# NAME_of_the_Game_NAND_Circuitry_v1.net
KiCad netlist of a schematic drawn in EAGLE
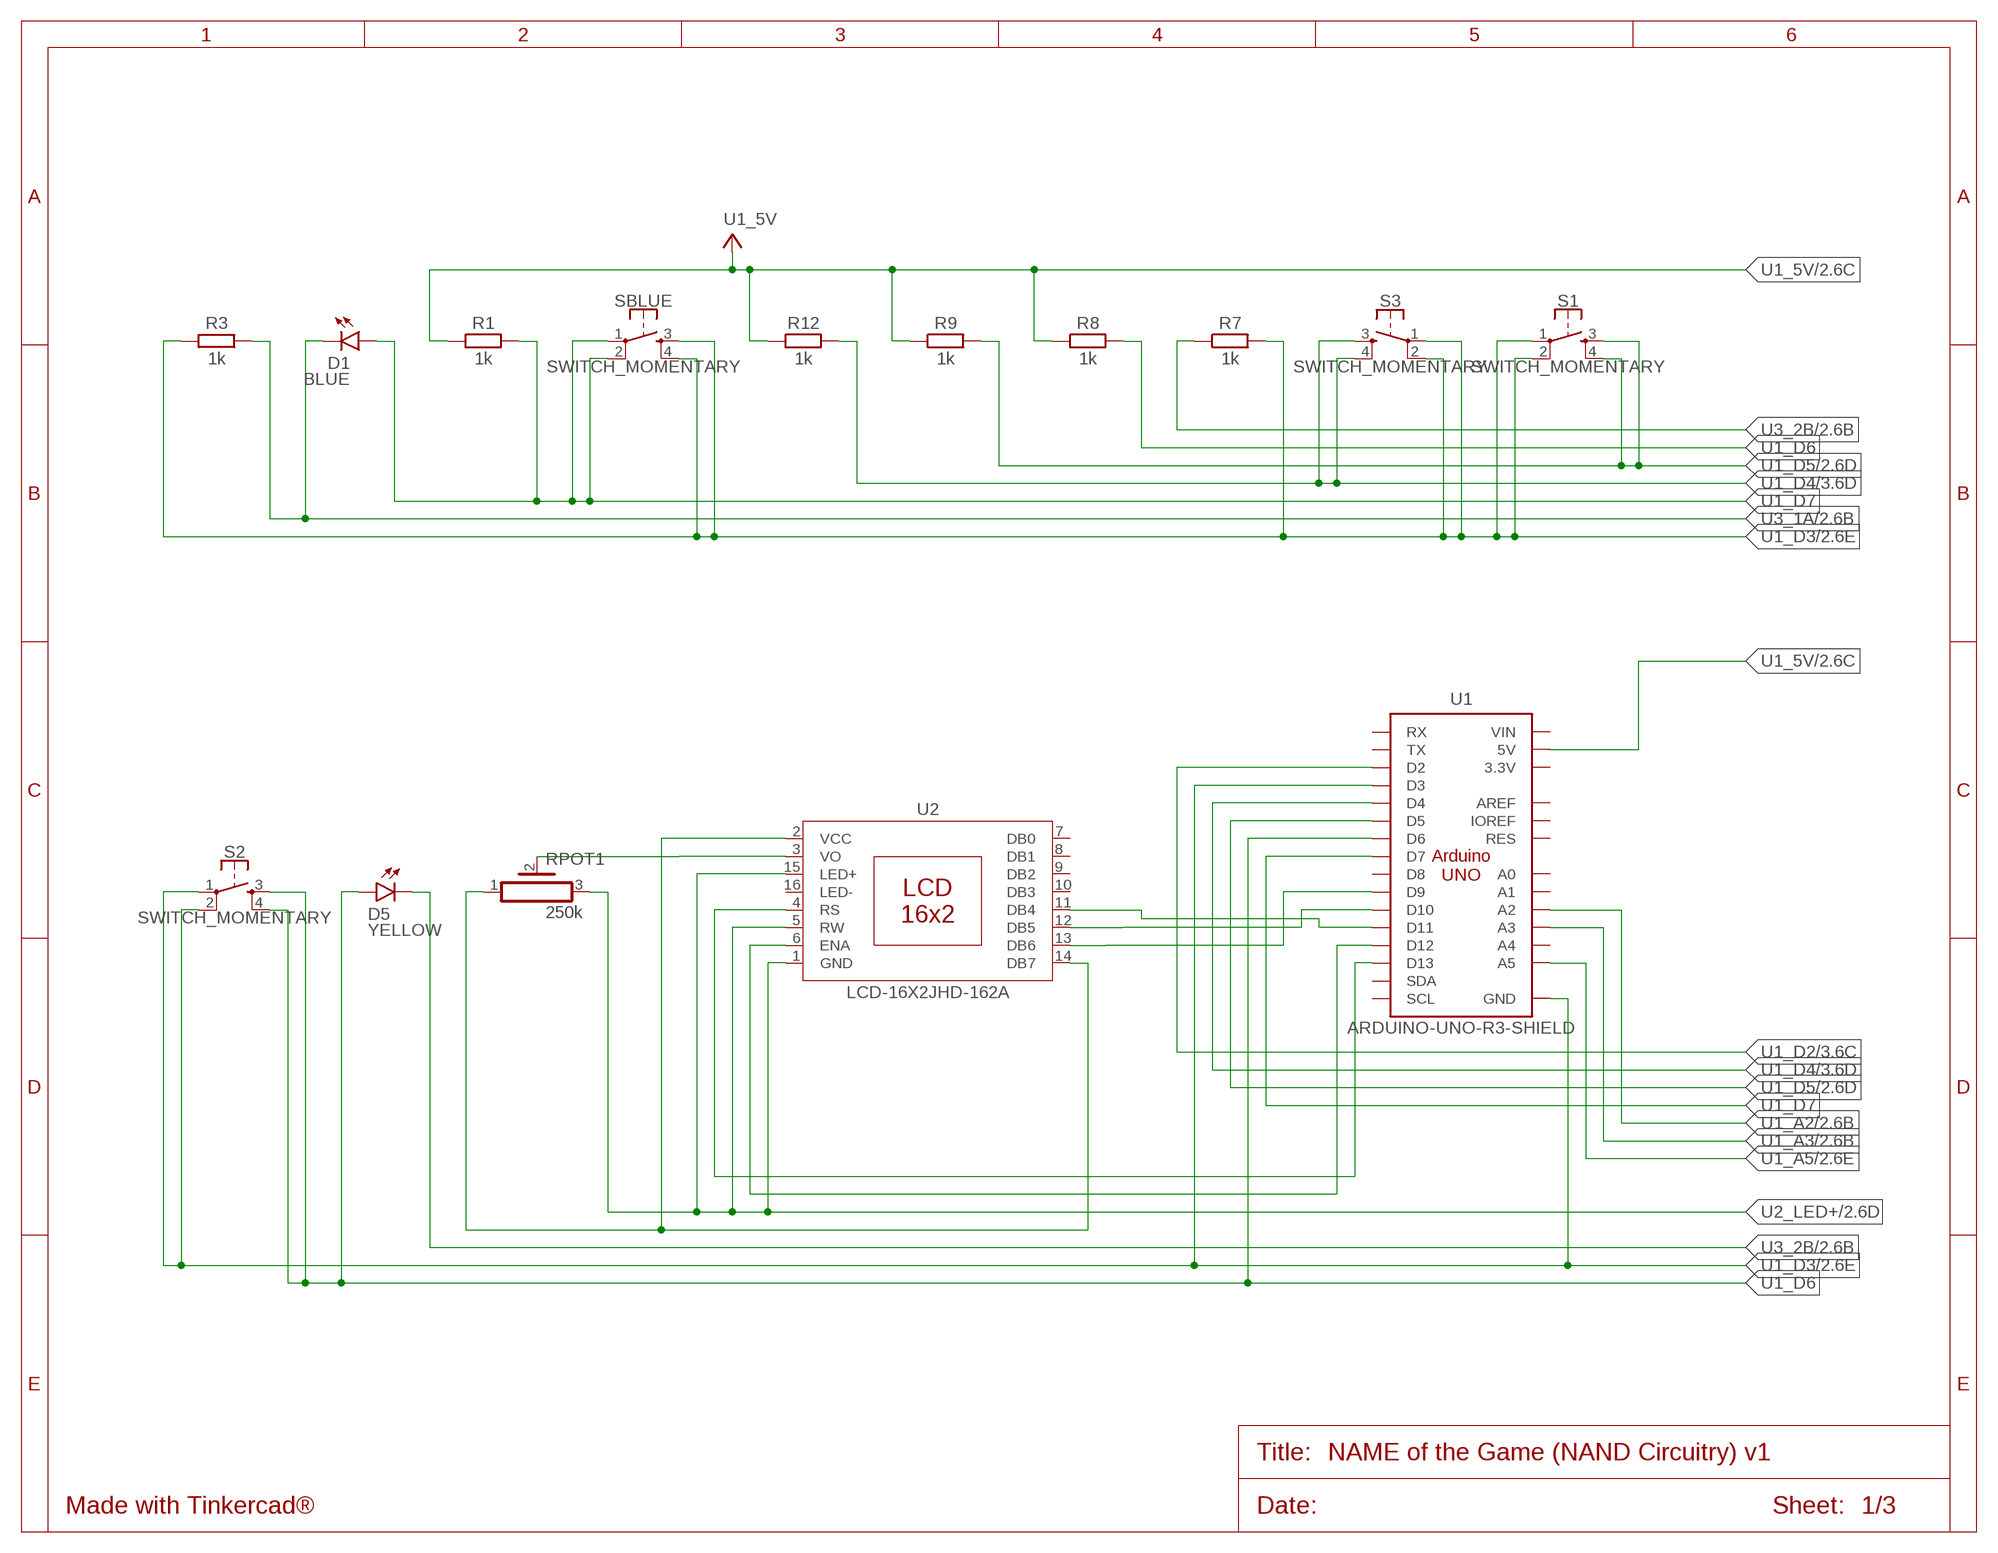
[diagram p0: schematic, sheet 1]
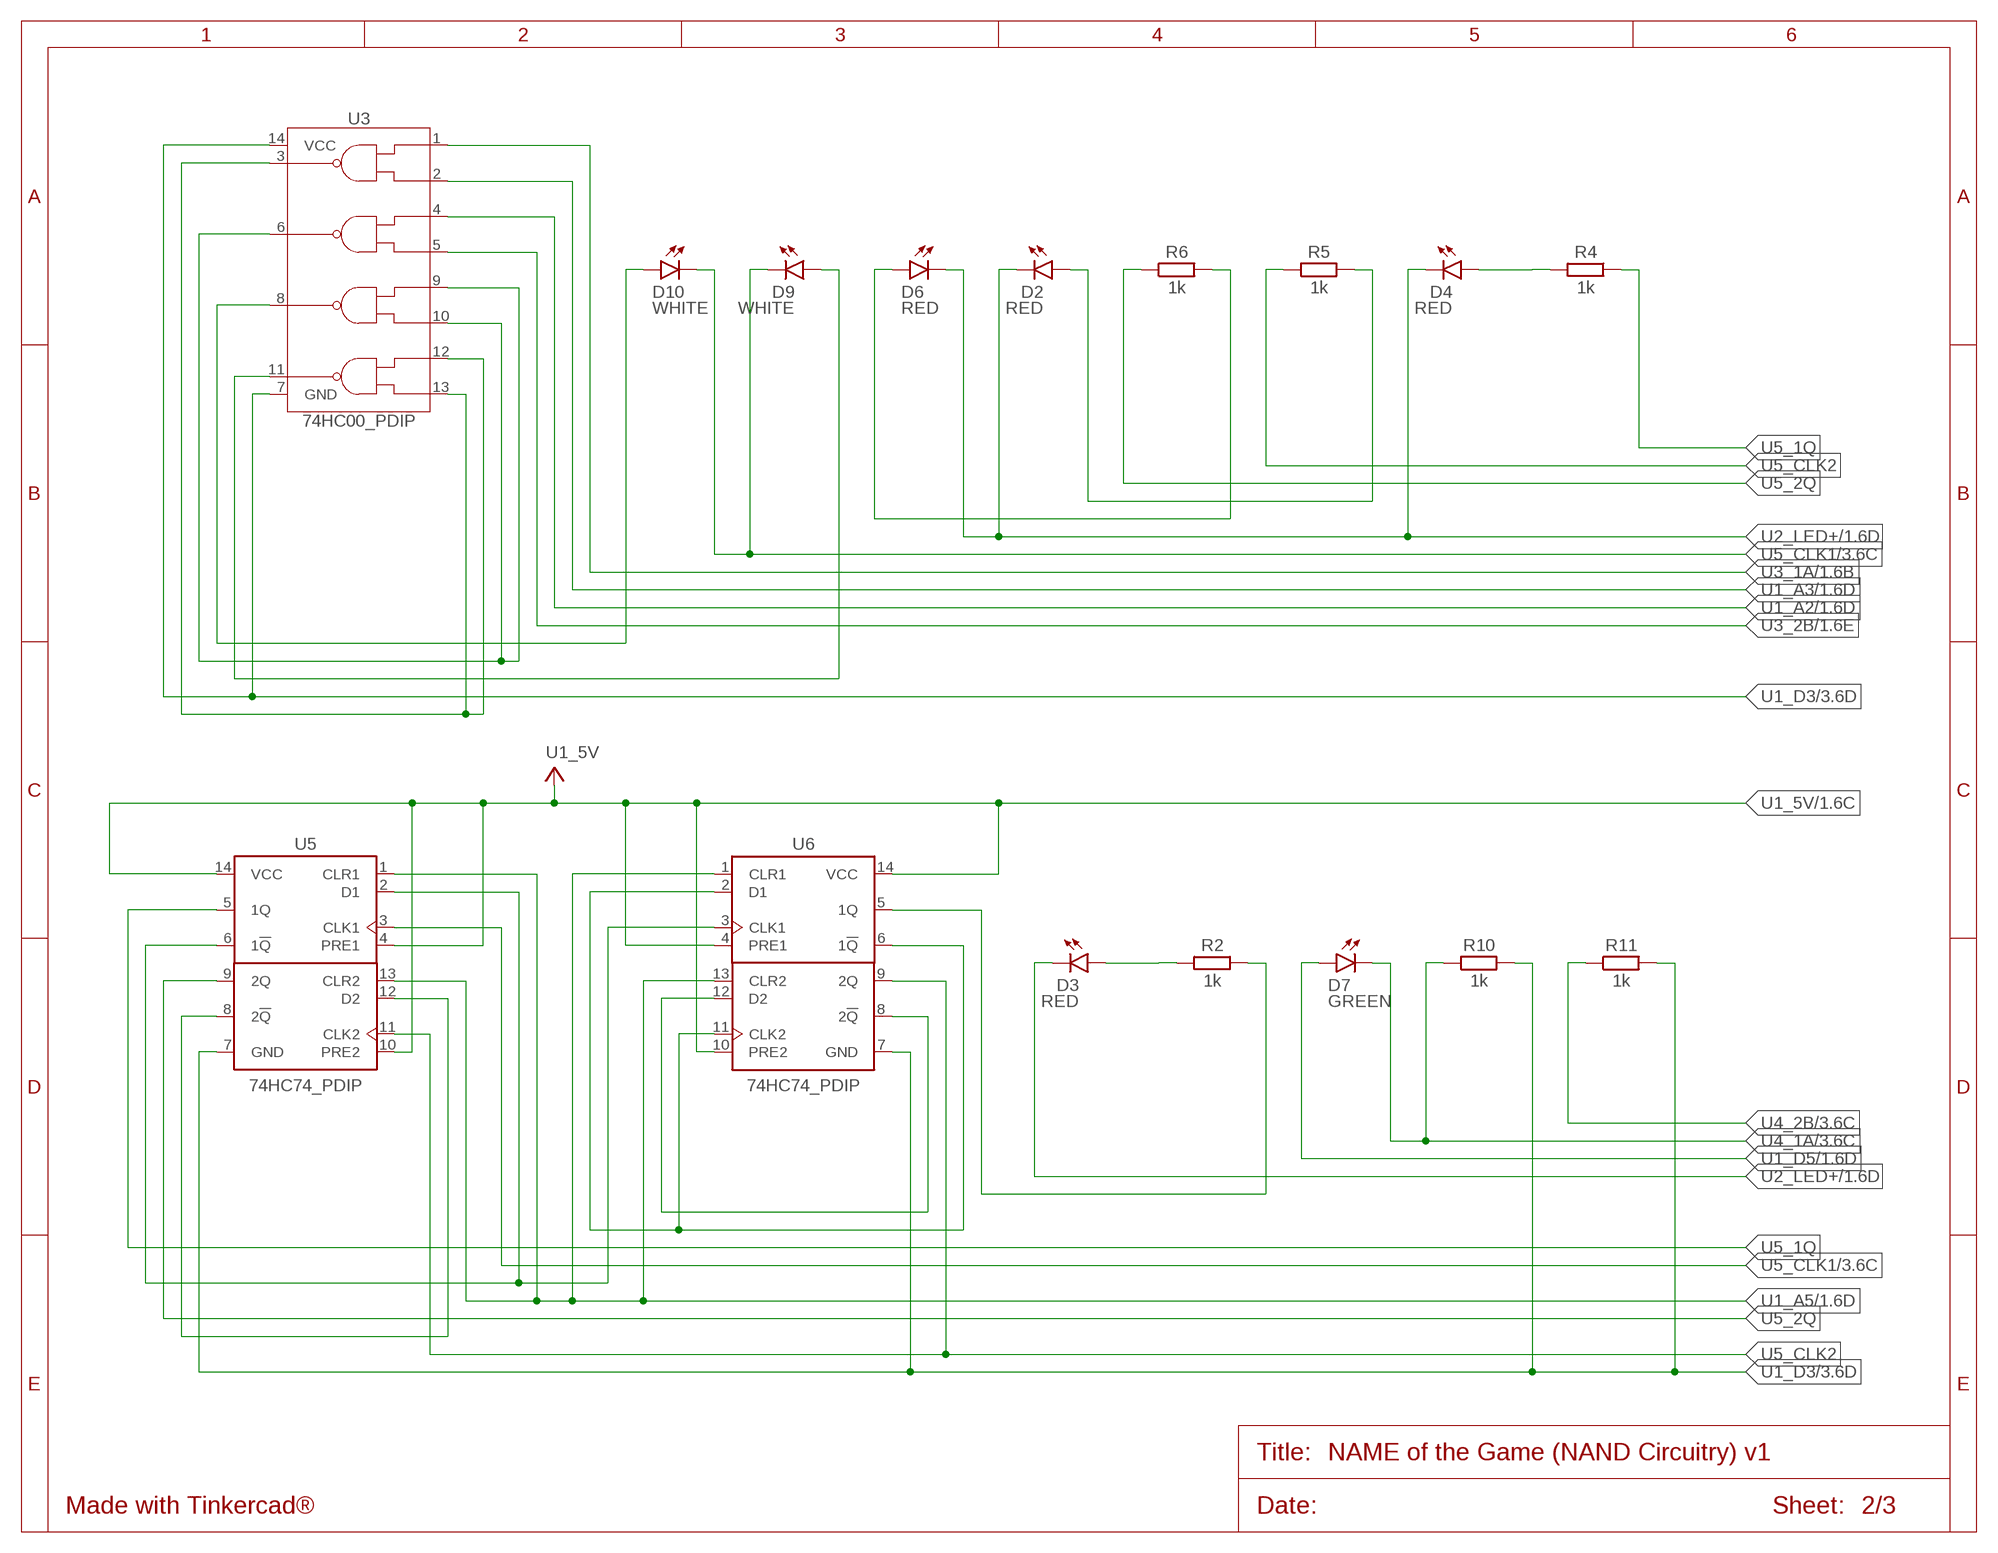
[diagram p1: schematic, sheet 2]
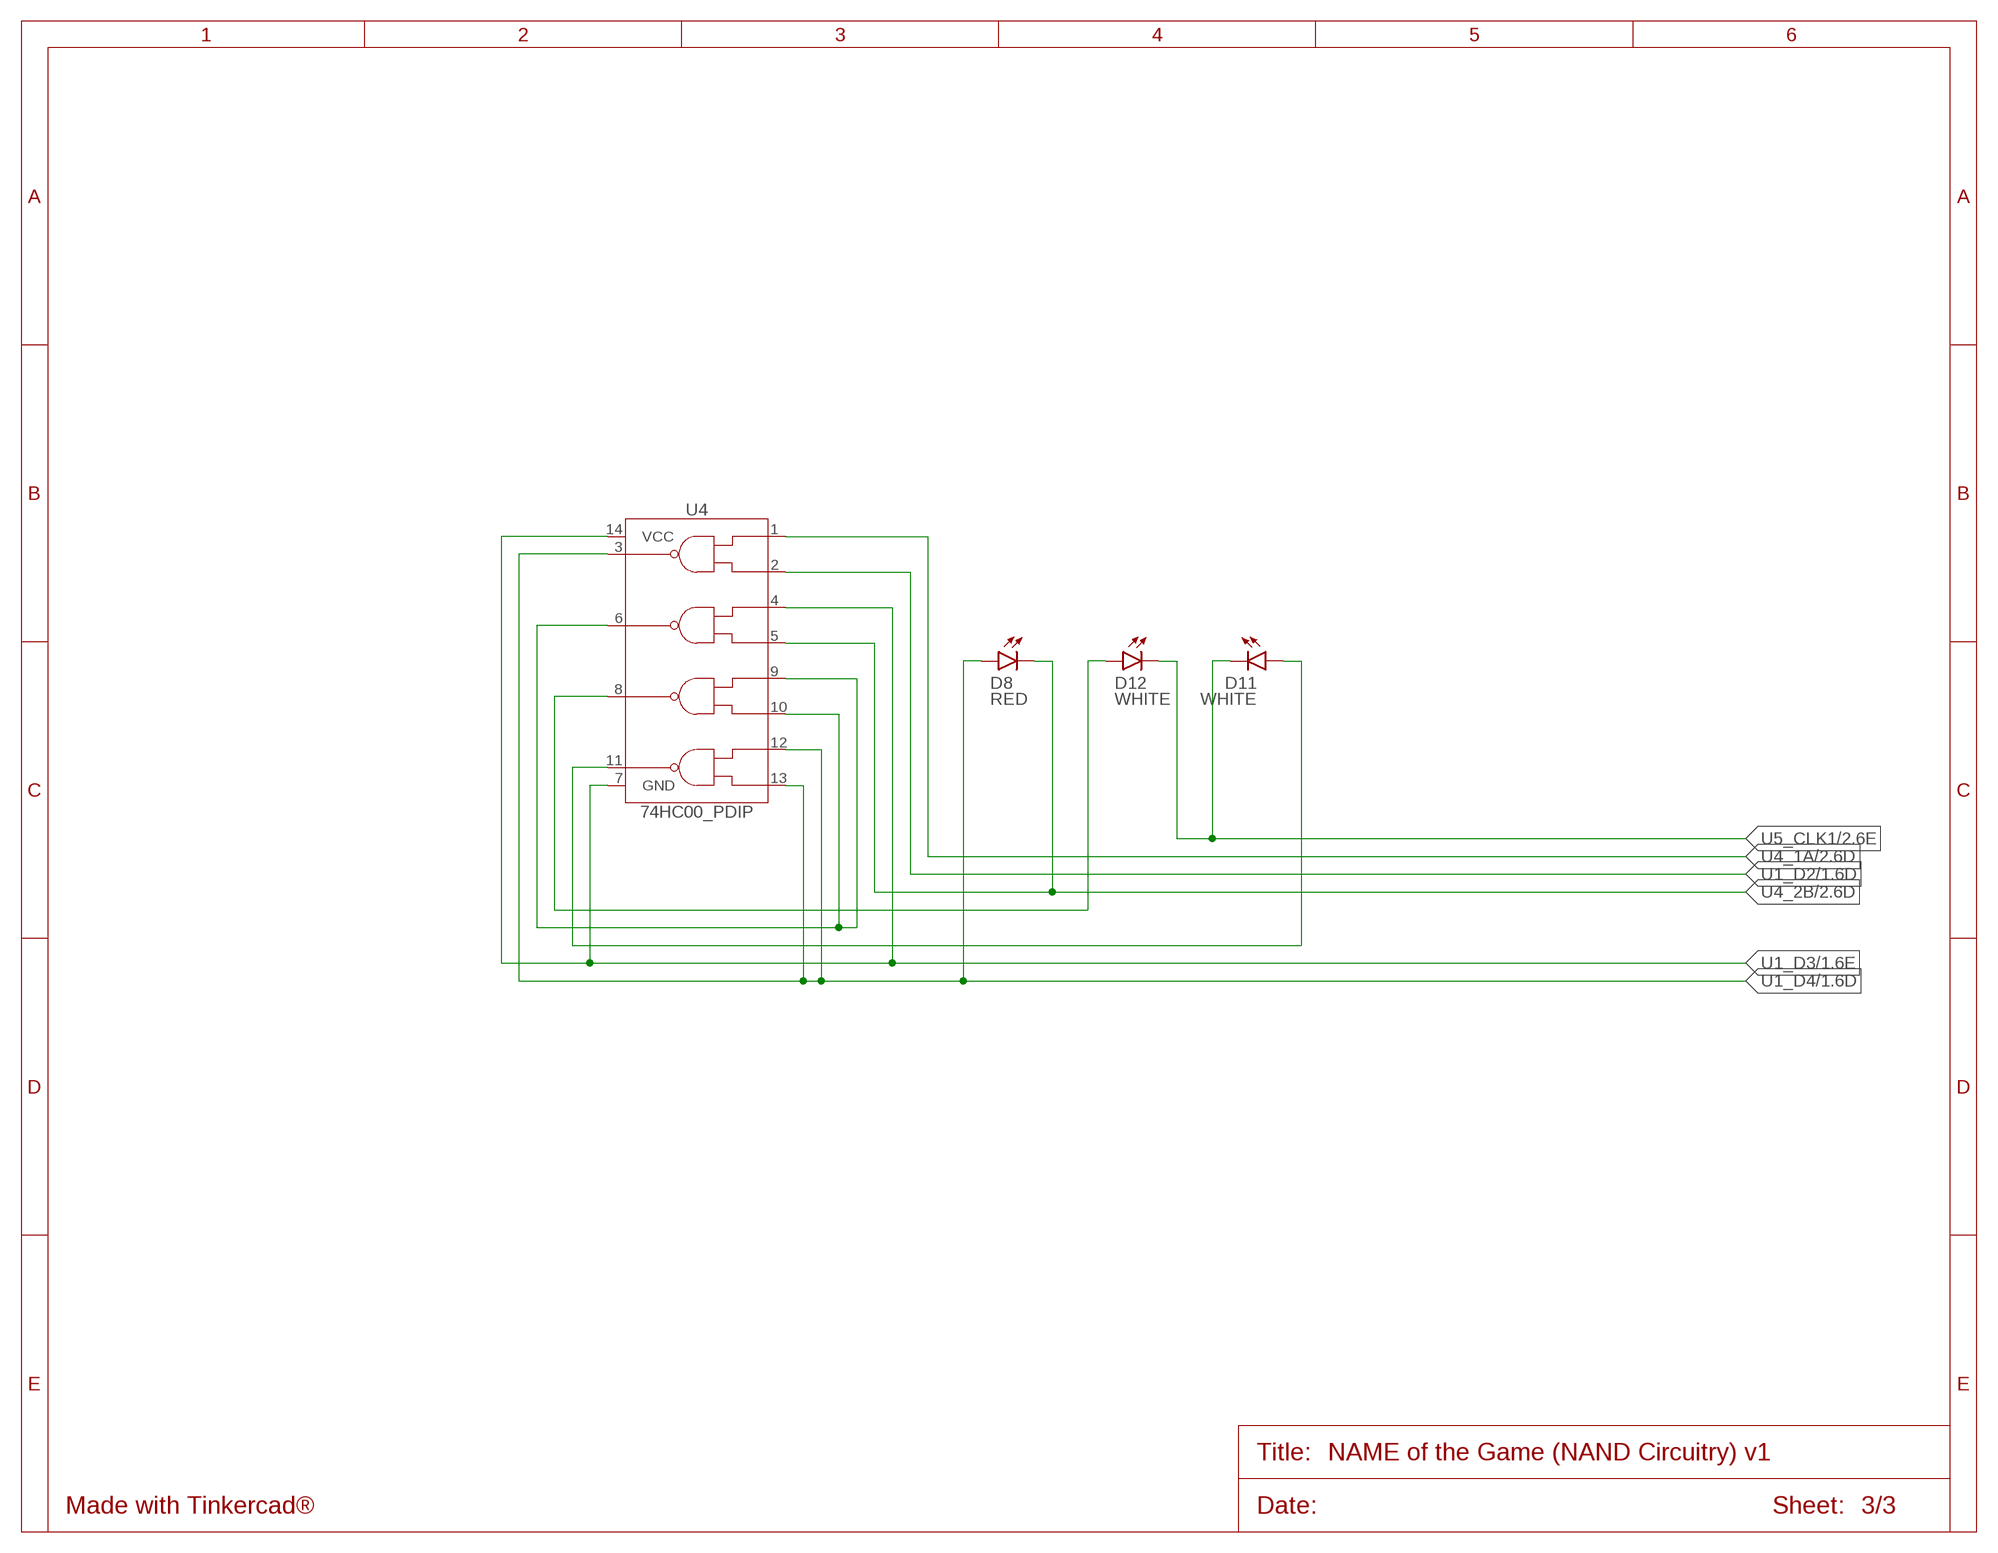
[diagram p2: schematic, sheet 3]

(export (version "E")
  (design (tool "Eeschema 10.0.6"))
  (components
    (comp (ref "D1")
      (value "BLUE")
      (footprint "eagle-import:LEDRD254W60D565H860B_B")
      (libsource (lib "eagle-import") (part "LED_RADIALBLUE_"))
    )
    (comp (ref "D5")
      (value "YELLOW")
      (footprint "eagle-import:LEDRD254W60D565H860B_Y")
      (libsource (lib "eagle-import") (part "LED_RADIALYELLOW_"))
    )
    (comp (ref "R1")
      (value "1k")
      (footprint "eagle-import:RESAD1016W63L850D250B")
      (libsource (lib "eagle-import") (part "RESISTOR_AXIAL-10.16MM-PITCH"))
    )
    (comp (ref "R3")
      (value "1k")
      (footprint "eagle-import:RESAD1016W63L850D250B")
      (libsource (lib "eagle-import") (part "RESISTOR_AXIAL-10.16MM-PITCH"))
    )
    (comp (ref "R7")
      (value "1k")
      (footprint "eagle-import:RESAD1016W63L850D250B")
      (libsource (lib "eagle-import") (part "RESISTOR_AXIAL-10.16MM-PITCH"))
    )
    (comp (ref "R8")
      (value "1k")
      (footprint "eagle-import:RESAD1016W63L850D250B")
      (libsource (lib "eagle-import") (part "RESISTOR_AXIAL-10.16MM-PITCH"))
    )
    (comp (ref "R9")
      (value "1k")
      (footprint "eagle-import:RESAD1016W63L850D250B")
      (libsource (lib "eagle-import") (part "RESISTOR_AXIAL-10.16MM-PITCH"))
    )
    (comp (ref "R12")
      (value "1k")
      (footprint "eagle-import:RESAD1016W63L850D250B")
      (libsource (lib "eagle-import") (part "RESISTOR_AXIAL-10.16MM-PITCH"))
    )
    (comp (ref "RPOT1")
      (value "250k")
      (footprint "eagle-import:HA-06-SM065")
      (libsource (lib "eagle-import") (part "POT_HA-06"))
    )
    (comp (ref "S1")
      (value "SWITCH_MOMENTARY")
      (footprint "eagle-import:SWITCH-MOMENTARY-PTH-6.5MM")
      (libsource (lib "eagle-import") (part "SWITCH_MOMENTARY"))
    )
    (comp (ref "S2")
      (value "SWITCH_MOMENTARY")
      (footprint "eagle-import:SWITCH-MOMENTARY-PTH-6.5MM")
      (libsource (lib "eagle-import") (part "SWITCH_MOMENTARY"))
    )
    (comp (ref "S3")
      (value "SWITCH_MOMENTARY")
      (footprint "eagle-import:SWITCH-MOMENTARY-PTH-6.5MM")
      (libsource (lib "eagle-import") (part "SWITCH_MOMENTARY"))
    )
    (comp (ref "SBLUE")
      (value "SWITCH_MOMENTARY")
      (footprint "eagle-import:SWITCH-MOMENTARY-PTH-6.5MM")
      (libsource (lib "eagle-import") (part "SWITCH_MOMENTARY"))
    )
    (comp (ref "U1")
      (value "ARDUINO-UNO-R3-SHIELD")
      (footprint "eagle-import:ARDUINO-UNO-R3-SHIELD")
      (libsource (lib "eagle-import") (part "ARDUINO-UNO-R3-SHIELD"))
    )
    (comp (ref "U2")
      (value "LCD-16X2JHD-162A")
      (footprint "eagle-import:JHD-162A")
      (libsource (lib "eagle-import") (part "LCD-16X2JHD-162A"))
    )
    (comp (ref "D8")
      (value "RED")
      (footprint "eagle-import:LEDRD254W60D565H860B")
      (libsource (lib "eagle-import") (part "LED_RADIALRED_"))
    )
    (comp (ref "D11")
      (value "WHITE")
      (footprint "eagle-import:LEDRD254W60D565H860B_W")
      (libsource (lib "eagle-import") (part "LED_RADIALWHITE_"))
    )
    (comp (ref "D12")
      (value "WHITE")
      (footprint "eagle-import:LEDRD254W60D565H860B_W")
      (libsource (lib "eagle-import") (part "LED_RADIALWHITE_"))
    )
    (comp (ref "U4")
      (value "74HC00_PDIP")
      (footprint "eagle-import:DIP762W53P254L1969H508Q14B")
      (libsource (lib "eagle-import") (part "74HC00_PDIP"))
    )
    (comp (ref "D2")
      (value "RED")
      (footprint "eagle-import:LEDRD254W60D565H860B")
      (libsource (lib "eagle-import") (part "LED_RADIALRED_"))
    )
    (comp (ref "D3")
      (value "RED")
      (footprint "eagle-import:LEDRD254W60D565H860B")
      (libsource (lib "eagle-import") (part "LED_RADIALRED_"))
    )
    (comp (ref "D4")
      (value "RED")
      (footprint "eagle-import:LEDRD254W60D565H860B")
      (libsource (lib "eagle-import") (part "LED_RADIALRED_"))
    )
    (comp (ref "D6")
      (value "RED")
      (footprint "eagle-import:LEDRD254W60D565H860B")
      (libsource (lib "eagle-import") (part "LED_RADIALRED_"))
    )
    (comp (ref "D7")
      (value "GREEN")
      (footprint "eagle-import:LEDRD254W60D565H860B_G")
      (libsource (lib "eagle-import") (part "LED_RADIALGREEN_"))
    )
    (comp (ref "D9")
      (value "WHITE")
      (footprint "eagle-import:LEDRD254W60D565H860B_W")
      (libsource (lib "eagle-import") (part "LED_RADIALWHITE_"))
    )
    (comp (ref "D10")
      (value "WHITE")
      (footprint "eagle-import:LEDRD254W60D565H860B_W")
      (libsource (lib "eagle-import") (part "LED_RADIALWHITE_"))
    )
    (comp (ref "R2")
      (value "1k")
      (footprint "eagle-import:RESAD1016W63L850D250B")
      (libsource (lib "eagle-import") (part "RESISTOR_AXIAL-10.16MM-PITCH"))
    )
    (comp (ref "R4")
      (value "1k")
      (footprint "eagle-import:RESAD1016W63L850D250B")
      (libsource (lib "eagle-import") (part "RESISTOR_AXIAL-10.16MM-PITCH"))
    )
    (comp (ref "R5")
      (value "1k")
      (footprint "eagle-import:RESAD1016W63L850D250B")
      (libsource (lib "eagle-import") (part "RESISTOR_AXIAL-10.16MM-PITCH"))
    )
    (comp (ref "R6")
      (value "1k")
      (footprint "eagle-import:RESAD1016W63L850D250B")
      (libsource (lib "eagle-import") (part "RESISTOR_AXIAL-10.16MM-PITCH"))
    )
    (comp (ref "R10")
      (value "1k")
      (footprint "eagle-import:RESAD1016W63L850D250B")
      (libsource (lib "eagle-import") (part "RESISTOR_AXIAL-10.16MM-PITCH"))
    )
    (comp (ref "R11")
      (value "1k")
      (footprint "eagle-import:RESAD1016W63L850D250B")
      (libsource (lib "eagle-import") (part "RESISTOR_AXIAL-10.16MM-PITCH"))
    )
    (comp (ref "U3")
      (value "74HC00_PDIP")
      (footprint "eagle-import:DIP762W53P254L1969H508Q14B")
      (libsource (lib "eagle-import") (part "74HC00_PDIP"))
    )
    (comp (ref "U5")
      (value "74HC74_PDIP")
      (footprint "eagle-import:DIP762W53P254L1969H508Q14B")
      (libsource (lib "eagle-import") (part "74HC74_PDIP"))
    )
    (comp (ref "U6")
      (value "74HC74_PDIP")
      (footprint "eagle-import:DIP762W53P254L1969H508Q14B")
      (libsource (lib "eagle-import") (part "74HC74_PDIP"))
    )
  )
  (nets
    (net (code "1") (name "Net-(D2-A)") (class "Default")
      (node (ref "D2") (pin "1") (pinfunction "A_1") (pintype "passive"))
      (node (ref "R5") (pin "2") (pinfunction "2_2") (pintype "passive"))
    )
    (net (code "2") (name "Net-(D3-A)") (class "Default")
      (node (ref "D3") (pin "1") (pinfunction "A_1") (pintype "passive"))
      (node (ref "R2") (pin "2") (pinfunction "2_2") (pintype "passive"))
    )
    (net (code "3") (name "Net-(D4-A)") (class "Default")
      (node (ref "D4") (pin "1") (pinfunction "A_1") (pintype "passive"))
      (node (ref "R4") (pin "2") (pinfunction "2_2") (pintype "passive"))
    )
    (net (code "4") (name "Net-(D6-A)") (class "Default")
      (node (ref "D6") (pin "1") (pinfunction "A_1") (pintype "passive"))
      (node (ref "R6") (pin "2") (pinfunction "2_2") (pintype "passive"))
    )
    (net (code "5") (name "Net-(D9-A)") (class "Default")
      (node (ref "D9") (pin "1") (pinfunction "A_1") (pintype "passive"))
      (node (ref "U3") (pin "11") (pinfunction "4Y_11") (pintype "output"))
    )
    (net (code "6") (name "Net-(D10-A)") (class "Default")
      (node (ref "D10") (pin "1") (pinfunction "A_1") (pintype "passive"))
      (node (ref "U3") (pin "8") (pinfunction "3Y_8") (pintype "output"))
    )
    (net (code "7") (name "Net-(D11-A)") (class "Default")
      (node (ref "D11") (pin "1") (pinfunction "A_1") (pintype "passive"))
      (node (ref "U4") (pin "11") (pinfunction "4Y_11") (pintype "output"))
    )
    (net (code "8") (name "Net-(D12-A)") (class "Default")
      (node (ref "D12") (pin "1") (pinfunction "A_1") (pintype "passive"))
      (node (ref "U4") (pin "8") (pinfunction "3Y_8") (pintype "output"))
    )
    (net (code "9") (name "Net-(RPOT1-P$1)") (class "Default")
      (node (ref "RPOT1") (pin "1") (pinfunction "P$1_1") (pintype "passive"))
      (node (ref "U2") (pin "14") (pinfunction "DB7_14") (pintype "bidirectional"))
      (node (ref "U2") (pin "2") (pinfunction "VCC_2") (pintype "bidirectional"))
    )
    (net (code "10") (name "Net-(RPOT1-P$2)") (class "Default")
      (node (ref "RPOT1") (pin "2") (pinfunction "P$2_2") (pintype "passive"))
      (node (ref "U2") (pin "3") (pinfunction "VO_3") (pintype "bidirectional"))
    )
    (net (code "11") (name "Net-(U2-DB4)") (class "Default")
      (node (ref "U1") (pin "D11") (pinfunction "D11_D11") (pintype "bidirectional"))
      (node (ref "U2") (pin "11") (pinfunction "DB4_11") (pintype "bidirectional"))
    )
    (net (code "12") (name "Net-(U2-DB5)") (class "Default")
      (node (ref "U1") (pin "D10") (pinfunction "D10_D10") (pintype "bidirectional"))
      (node (ref "U2") (pin "12") (pinfunction "DB5_12") (pintype "bidirectional"))
    )
    (net (code "13") (name "Net-(U2-DB6)") (class "Default")
      (node (ref "U1") (pin "D9") (pinfunction "D9_D9") (pintype "bidirectional"))
      (node (ref "U2") (pin "13") (pinfunction "DB6_13") (pintype "bidirectional"))
    )
    (net (code "14") (name "Net-(U2-ENA)") (class "Default")
      (node (ref "U1") (pin "D12") (pinfunction "D12_D12") (pintype "bidirectional"))
      (node (ref "U2") (pin "6") (pinfunction "ENA_6") (pintype "bidirectional"))
    )
    (net (code "15") (name "Net-(U2-RS)") (class "Default")
      (node (ref "U1") (pin "D13") (pinfunction "D13_D13") (pintype "bidirectional"))
      (node (ref "U2") (pin "4") (pinfunction "RS_4") (pintype "bidirectional"))
    )
    (net (code "16") (name "Net-(U3-1Y)") (class "Default")
      (node (ref "U3") (pin "12") (pinfunction "4A_12") (pintype "input"))
      (node (ref "U3") (pin "13") (pinfunction "4B_13") (pintype "input"))
      (node (ref "U3") (pin "3") (pinfunction "1Y_3") (pintype "output"))
    )
    (net (code "17") (name "Net-(U3-2Y)") (class "Default")
      (node (ref "U3") (pin "10") (pinfunction "3B_10") (pintype "input"))
      (node (ref "U3") (pin "6") (pinfunction "2Y_6") (pintype "output"))
      (node (ref "U3") (pin "9") (pinfunction "3A_9") (pintype "input"))
    )
    (net (code "18") (name "Net-(U4-2Y)") (class "Default")
      (node (ref "U4") (pin "10") (pinfunction "3B_10") (pintype "input"))
      (node (ref "U4") (pin "6") (pinfunction "2Y_6") (pintype "output"))
      (node (ref "U4") (pin "9") (pinfunction "3A_9") (pintype "input"))
    )
    (net (code "19") (name "Net-(U5-1~{Q})") (class "Default")
      (node (ref "U5") (pin "2") (pinfunction "D1_2") (pintype "input"))
      (node (ref "U5") (pin "6") (pinfunction "1~{Q}_6") (pintype "output"))
      (node (ref "U6") (pin "3") (pinfunction "CLK1_3") (pintype "input"))
    )
    (net (code "20") (name "Net-(U5-2~{Q})") (class "Default")
      (node (ref "U5") (pin "12") (pinfunction "D2_12") (pintype "input"))
      (node (ref "U5") (pin "8") (pinfunction "2~{Q}_8") (pintype "output"))
    )
    (net (code "21") (name "Net-(U6-1Q)") (class "Default")
      (node (ref "R2") (pin "1") (pinfunction "1_1") (pintype "passive"))
      (node (ref "U6") (pin "5") (pinfunction "1Q_5") (pintype "output"))
    )
    (net (code "22") (name "Net-(U6-1~{Q})") (class "Default")
      (node (ref "U6") (pin "11") (pinfunction "CLK2_11") (pintype "input"))
      (node (ref "U6") (pin "2") (pinfunction "D1_2") (pintype "input"))
      (node (ref "U6") (pin "6") (pinfunction "1~{Q}_6") (pintype "output"))
    )
    (net (code "23") (name "Net-(U6-2~{Q})") (class "Default")
      (node (ref "U6") (pin "12") (pinfunction "D2_12") (pintype "input"))
      (node (ref "U6") (pin "8") (pinfunction "2~{Q}_8") (pintype "output"))
    )
    (net (code "24") (name "U1_5V") (class "Default")
      (node (ref "R1") (pin "1") (pinfunction "1_1") (pintype "passive"))
      (node (ref "R12") (pin "1") (pinfunction "1_1") (pintype "passive"))
      (node (ref "R8") (pin "1") (pinfunction "1_1") (pintype "passive"))
      (node (ref "R9") (pin "1") (pinfunction "1_1") (pintype "passive"))
      (node (ref "U1") (pin "5V") (pinfunction "5V_5V") (pintype "bidirectional"))
      (node (ref "U5") (pin "10") (pinfunction "PRE2_10") (pintype "input"))
      (node (ref "U5") (pin "14") (pinfunction "VCC_14") (pintype "bidirectional"))
      (node (ref "U5") (pin "4") (pinfunction "PRE1_4") (pintype "input"))
      (node (ref "U6") (pin "10") (pinfunction "PRE2_10") (pintype "input"))
      (node (ref "U6") (pin "14") (pinfunction "VCC_14") (pintype "bidirectional"))
      (node (ref "U6") (pin "4") (pinfunction "PRE1_4") (pintype "input"))
    )
    (net (code "25") (name "U1_A2") (class "Default")
      (node (ref "U1") (pin "A2") (pinfunction "A2_A2") (pintype "bidirectional"))
      (node (ref "U3") (pin "4") (pinfunction "2A_4") (pintype "input"))
    )
    (net (code "26") (name "U1_A3") (class "Default")
      (node (ref "U1") (pin "A3") (pinfunction "A3_A3") (pintype "bidirectional"))
      (node (ref "U3") (pin "2") (pinfunction "1B_2") (pintype "input"))
    )
    (net (code "27") (name "U1_A5") (class "Default")
      (node (ref "U1") (pin "A5") (pinfunction "A5_A5") (pintype "bidirectional"))
      (node (ref "U5") (pin "1") (pinfunction "CLR1_1") (pintype "input"))
      (node (ref "U5") (pin "13") (pinfunction "CLR2_13") (pintype "input"))
      (node (ref "U6") (pin "1") (pinfunction "CLR1_1") (pintype "input"))
      (node (ref "U6") (pin "13") (pinfunction "CLR2_13") (pintype "input"))
    )
    (net (code "28") (name "U1_D2") (class "Default")
      (node (ref "U1") (pin "D2") (pinfunction "D2_D2") (pintype "bidirectional"))
      (node (ref "U4") (pin "2") (pinfunction "1B_2") (pintype "input"))
    )
    (net (code "29") (name "U1_D3") (class "Default")
      (node (ref "R10") (pin "2") (pinfunction "2_2") (pintype "passive"))
      (node (ref "R11") (pin "2") (pinfunction "2_2") (pintype "passive"))
      (node (ref "R3") (pin "2") (pinfunction "2_2") (pintype "passive"))
      (node (ref "R7") (pin "2") (pinfunction "2_2") (pintype "passive"))
      (node (ref "S1") (pin "1") (pinfunction "1_1") (pintype "passive"))
      (node (ref "S1") (pin "2") (pinfunction "2_2") (pintype "passive"))
      (node (ref "S2") (pin "1") (pinfunction "1_1") (pintype "passive"))
      (node (ref "S2") (pin "2") (pinfunction "2_2") (pintype "passive"))
      (node (ref "S3") (pin "1") (pinfunction "1_1") (pintype "passive"))
      (node (ref "S3") (pin "2") (pinfunction "2_2") (pintype "passive"))
      (node (ref "SBLUE") (pin "3") (pinfunction "3_3") (pintype "passive"))
      (node (ref "SBLUE") (pin "4") (pinfunction "4_4") (pintype "passive"))
      (node (ref "U1") (pin "D3") (pinfunction "D3_D3") (pintype "bidirectional"))
      (node (ref "U1") (pin "GND@0") (pinfunction "GND_GND@0") (pintype "bidirectional"))
      (node (ref "U1") (pin "GND@1") (pinfunction "GND_GND@1") (pintype "bidirectional"))
      (node (ref "U1") (pin "GND@2") (pinfunction "GND_GND@2") (pintype "bidirectional"))
      (node (ref "U3") (pin "14") (pinfunction "VCC_14") (pintype "bidirectional"))
      (node (ref "U3") (pin "7") (pinfunction "GND_7") (pintype "bidirectional"))
      (node (ref "U4") (pin "14") (pinfunction "VCC_14") (pintype "bidirectional"))
      (node (ref "U4") (pin "4") (pinfunction "2A_4") (pintype "input"))
      (node (ref "U4") (pin "7") (pinfunction "GND_7") (pintype "bidirectional"))
      (node (ref "U5") (pin "7") (pinfunction "GND_7") (pintype "bidirectional"))
      (node (ref "U6") (pin "7") (pinfunction "GND_7") (pintype "bidirectional"))
    )
    (net (code "30") (name "U1_D4") (class "Default")
      (node (ref "D8") (pin "1") (pinfunction "A_1") (pintype "passive"))
      (node (ref "R12") (pin "2") (pinfunction "2_2") (pintype "passive"))
      (node (ref "S3") (pin "3") (pinfunction "3_3") (pintype "passive"))
      (node (ref "S3") (pin "4") (pinfunction "4_4") (pintype "passive"))
      (node (ref "U1") (pin "D4") (pinfunction "D4_D4") (pintype "bidirectional"))
      (node (ref "U4") (pin "12") (pinfunction "4A_12") (pintype "input"))
      (node (ref "U4") (pin "13") (pinfunction "4B_13") (pintype "input"))
      (node (ref "U4") (pin "3") (pinfunction "1Y_3") (pintype "output"))
    )
    (net (code "31") (name "U1_D5") (class "Default")
      (node (ref "D7") (pin "1") (pinfunction "A_1") (pintype "passive"))
      (node (ref "R9") (pin "2") (pinfunction "2_2") (pintype "passive"))
      (node (ref "S1") (pin "3") (pinfunction "3_3") (pintype "passive"))
      (node (ref "S1") (pin "4") (pinfunction "4_4") (pintype "passive"))
      (node (ref "U1") (pin "D5") (pinfunction "D5_D5") (pintype "bidirectional"))
    )
    (net (code "32") (name "U1_D6") (class "Default")
      (node (ref "D5") (pin "1") (pinfunction "A_1") (pintype "passive"))
      (node (ref "R8") (pin "2") (pinfunction "2_2") (pintype "passive"))
      (node (ref "S2") (pin "3") (pinfunction "3_3") (pintype "passive"))
      (node (ref "S2") (pin "4") (pinfunction "4_4") (pintype "passive"))
      (node (ref "U1") (pin "D6") (pinfunction "D6_D6") (pintype "bidirectional"))
    )
    (net (code "33") (name "U1_D7") (class "Default")
      (node (ref "D1") (pin "1") (pinfunction "A_1") (pintype "passive"))
      (node (ref "R1") (pin "2") (pinfunction "2_2") (pintype "passive"))
      (node (ref "SBLUE") (pin "1") (pinfunction "1_1") (pintype "passive"))
      (node (ref "SBLUE") (pin "2") (pinfunction "2_2") (pintype "passive"))
      (node (ref "U1") (pin "D7") (pinfunction "D7_D7") (pintype "bidirectional"))
    )
    (net (code "34") (name "U2_LED+") (class "Default")
      (node (ref "D2") (pin "2") (pinfunction "C_2") (pintype "passive"))
      (node (ref "D3") (pin "2") (pinfunction "C_2") (pintype "passive"))
      (node (ref "D4") (pin "2") (pinfunction "C_2") (pintype "passive"))
      (node (ref "D6") (pin "2") (pinfunction "C_2") (pintype "passive"))
      (node (ref "RPOT1") (pin "3") (pinfunction "P$3_3") (pintype "passive"))
      (node (ref "U2") (pin "1") (pinfunction "GND_1") (pintype "bidirectional"))
      (node (ref "U2") (pin "15") (pinfunction "LED+_15") (pintype "bidirectional"))
      (node (ref "U2") (pin "5") (pinfunction "RW_5") (pintype "bidirectional"))
    )
    (net (code "35") (name "U3_1A") (class "Default")
      (node (ref "D1") (pin "2") (pinfunction "C_2") (pintype "passive"))
      (node (ref "R3") (pin "1") (pinfunction "1_1") (pintype "passive"))
      (node (ref "U3") (pin "1") (pinfunction "1A_1") (pintype "input"))
    )
    (net (code "36") (name "U3_2B") (class "Default")
      (node (ref "D5") (pin "2") (pinfunction "C_2") (pintype "passive"))
      (node (ref "R7") (pin "1") (pinfunction "1_1") (pintype "passive"))
      (node (ref "U3") (pin "5") (pinfunction "2B_5") (pintype "input"))
    )
    (net (code "37") (name "U4_1A") (class "Default")
      (node (ref "D7") (pin "2") (pinfunction "C_2") (pintype "passive"))
      (node (ref "R10") (pin "1") (pinfunction "1_1") (pintype "passive"))
      (node (ref "U4") (pin "1") (pinfunction "1A_1") (pintype "input"))
    )
    (net (code "38") (name "U4_2B") (class "Default")
      (node (ref "D8") (pin "2") (pinfunction "C_2") (pintype "passive"))
      (node (ref "R11") (pin "1") (pinfunction "1_1") (pintype "passive"))
      (node (ref "U4") (pin "5") (pinfunction "2B_5") (pintype "input"))
    )
    (net (code "39") (name "U5_1Q") (class "Default")
      (node (ref "R4") (pin "1") (pinfunction "1_1") (pintype "passive"))
      (node (ref "U5") (pin "5") (pinfunction "1Q_5") (pintype "output"))
    )
    (net (code "40") (name "U5_2Q") (class "Default")
      (node (ref "R6") (pin "1") (pinfunction "1_1") (pintype "passive"))
      (node (ref "U5") (pin "9") (pinfunction "2Q_9") (pintype "output"))
    )
    (net (code "41") (name "U5_CLK1") (class "Default")
      (node (ref "D10") (pin "2") (pinfunction "C_2") (pintype "passive"))
      (node (ref "D11") (pin "2") (pinfunction "C_2") (pintype "passive"))
      (node (ref "D12") (pin "2") (pinfunction "C_2") (pintype "passive"))
      (node (ref "D9") (pin "2") (pinfunction "C_2") (pintype "passive"))
      (node (ref "U5") (pin "3") (pinfunction "CLK1_3") (pintype "input"))
    )
    (net (code "42") (name "U5_CLK2") (class "Default")
      (node (ref "R5") (pin "1") (pinfunction "1_1") (pintype "passive"))
      (node (ref "U5") (pin "11") (pinfunction "CLK2_11") (pintype "input"))
      (node (ref "U6") (pin "9") (pinfunction "2Q_9") (pintype "output"))
    )
    (net (code "43") (name "unconnected-(U1-Pad3.3V)") (class "Default")
      (node (ref "U1") (pin "3.3V") (pinfunction "3.3V_3.3V") (pintype "bidirectional"))
    )
    (net (code "44") (name "unconnected-(U1-PadA0)") (class "Default")
      (node (ref "U1") (pin "A0") (pinfunction "A0_A0") (pintype "bidirectional"))
    )
    (net (code "45") (name "unconnected-(U1-PadA1)") (class "Default")
      (node (ref "U1") (pin "A1") (pinfunction "A1_A1") (pintype "bidirectional"))
    )
    (net (code "46") (name "unconnected-(U1-PadA4)") (class "Default")
      (node (ref "U1") (pin "A4") (pinfunction "A4_A4") (pintype "bidirectional"))
    )
    (net (code "47") (name "unconnected-(U1-PadAREF)") (class "Default")
      (node (ref "U1") (pin "AREF") (pinfunction "AREF_AREF") (pintype "bidirectional"))
    )
    (net (code "48") (name "unconnected-(U1-PadD8)") (class "Default")
      (node (ref "U1") (pin "D8") (pinfunction "D8_D8") (pintype "bidirectional"))
    )
    (net (code "49") (name "unconnected-(U1-PadIOREF)") (class "Default")
      (node (ref "U1") (pin "IOREF") (pinfunction "IOREF_IOREF") (pintype "bidirectional"))
    )
    (net (code "50") (name "unconnected-(U1-PadRES)") (class "Default")
      (node (ref "U1") (pin "RES") (pinfunction "RES_RES") (pintype "bidirectional"))
    )
    (net (code "51") (name "unconnected-(U1-PadRX)") (class "Default")
      (node (ref "U1") (pin "RX") (pinfunction "RX_RX") (pintype "bidirectional"))
    )
    (net (code "52") (name "unconnected-(U1-PadSCL)") (class "Default")
      (node (ref "U1") (pin "SCL") (pinfunction "SCL_SCL") (pintype "bidirectional"))
    )
    (net (code "53") (name "unconnected-(U1-PadSDA)") (class "Default")
      (node (ref "U1") (pin "SDA") (pinfunction "SDA_SDA") (pintype "bidirectional"))
    )
    (net (code "54") (name "unconnected-(U1-PadTX)") (class "Default")
      (node (ref "U1") (pin "TX") (pinfunction "TX_TX") (pintype "bidirectional"))
    )
    (net (code "55") (name "unconnected-(U1-PadVIN)") (class "Default")
      (node (ref "U1") (pin "VIN") (pinfunction "VIN_VIN") (pintype "bidirectional"))
    )
    (net (code "56") (name "unconnected-(U2-DB0-Pad7)") (class "Default")
      (node (ref "U2") (pin "7") (pinfunction "DB0_7") (pintype "bidirectional"))
    )
    (net (code "57") (name "unconnected-(U2-DB1-Pad8)") (class "Default")
      (node (ref "U2") (pin "8") (pinfunction "DB1_8") (pintype "bidirectional"))
    )
    (net (code "58") (name "unconnected-(U2-DB2-Pad9)") (class "Default")
      (node (ref "U2") (pin "9") (pinfunction "DB2_9") (pintype "bidirectional"))
    )
    (net (code "59") (name "unconnected-(U2-DB3-Pad10)") (class "Default")
      (node (ref "U2") (pin "10") (pinfunction "DB3_10") (pintype "bidirectional"))
    )
    (net (code "60") (name "unconnected-(U2-LED--Pad16)") (class "Default")
      (node (ref "U2") (pin "16") (pinfunction "LED-_16") (pintype "bidirectional"))
    )
  )
)
